# T2103_ValSouffle.net
KiCad netlist of a schematic drawn in EAGLE
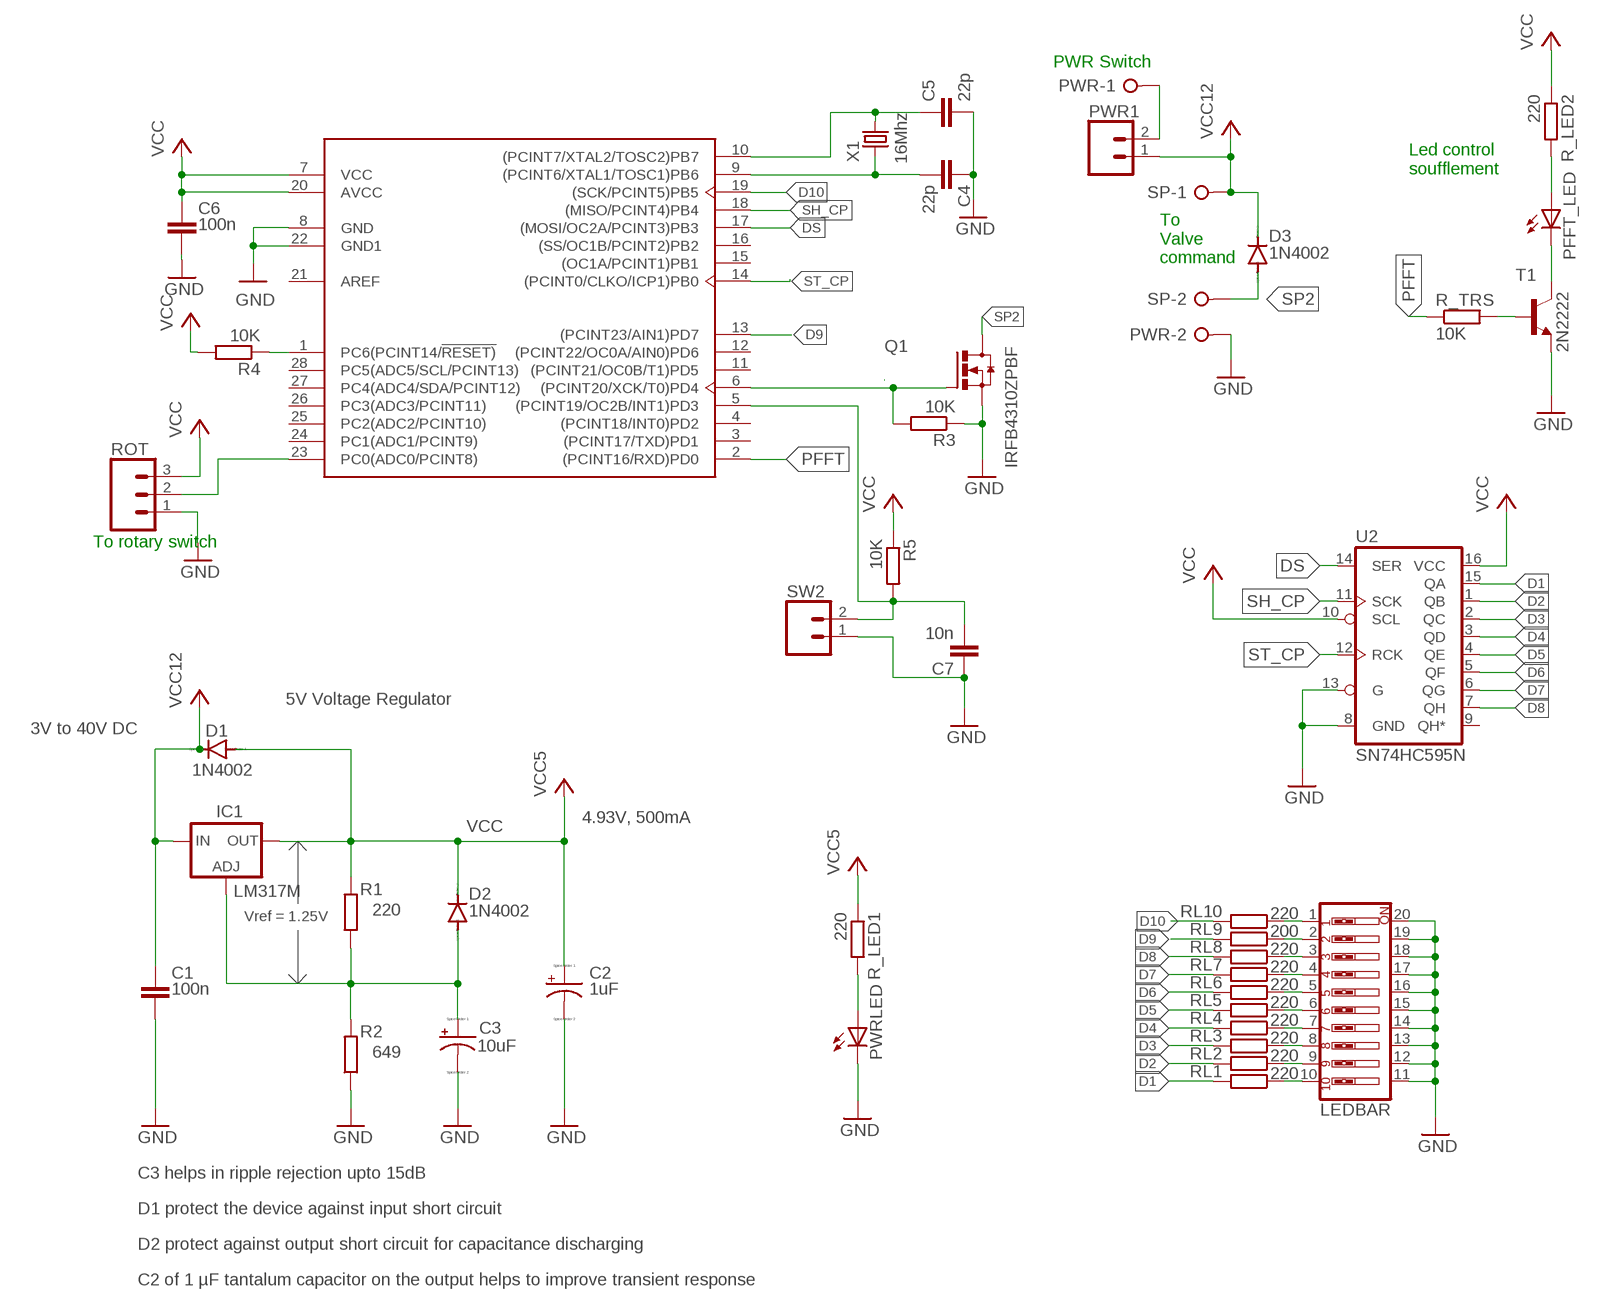
[diagram p0: schematic, sheet 1]

(export (version "E")
  (design (tool "Eeschema 10.0.6"))
  (components
    (comp (ref "C1")
      (value "100n")
      (footprint "eagle-import:C050-030X075")
      (libsource (lib "eagle-import") (part "C-EU050-030X075"))
    )
    (comp (ref "C2")
      (value "1uF")
      (footprint "eagle-import:E1,8-4")
      (libsource (lib "eagle-import") (part "CPOL-USE1.8-4"))
    )
    (comp (ref "C3")
      (value "10uF")
      (footprint "eagle-import:E1,8-4")
      (libsource (lib "eagle-import") (part "CPOL-USE1.8-4"))
    )
    (comp (ref "C4")
      (value "22p")
      (footprint "eagle-import:C025-025X050")
      (libsource (lib "eagle-import") (part "resistor_348_C-EU025-025X050"))
    )
    (comp (ref "C5")
      (value "22p")
      (footprint "eagle-import:C025-025X050")
      (libsource (lib "eagle-import") (part "resistor_348_C-EU025-025X050"))
    )
    (comp (ref "C6")
      (value "100n")
      (footprint "eagle-import:C050-030X075")
      (libsource (lib "eagle-import") (part "C-EU050-030X075"))
    )
    (comp (ref "C7")
      (value "10n")
      (footprint "eagle-import:C025-025X050")
      (libsource (lib "eagle-import") (part "resistor_348_C-EU025-025X050"))
    )
    (comp (ref "D1")
      (value "1N4002")
      (footprint "eagle-import:DO41-10")
      (libsource (lib "eagle-import") (part "1N4004"))
    )
    (comp (ref "D2")
      (value "1N4002")
      (footprint "eagle-import:DO41-10")
      (libsource (lib "eagle-import") (part "1N4004"))
    )
    (comp (ref "D3")
      (value "1N4002")
      (footprint "eagle-import:DO41-10")
      (libsource (lib "eagle-import") (part "1N4004"))
    )
    (comp (ref "IC1")
      (value "LM317MB")
      (footprint "eagle-import:TO220L1")
      (fields (field (name "PARTNUMBER") "LM317M"))
      (libsource (lib "eagle-import") (part "LM317?MB"))
    )
    (comp (ref "LEDBAR")
      (value "SW_DIP-10")
      (footprint "eagle-import:EDG-10")
      (libsource (lib "eagle-import") (part "SW_DIP-10"))
    )
    (comp (ref "PFFT_LED")
      (value "LED5MM")
      (footprint "eagle-import:LED5MM")
      (libsource (lib "eagle-import") (part "LED5MM"))
    )
    (comp (ref "PWR")
      (value "W237-02P")
      (footprint "eagle-import:W237-132")
      (libsource (lib "eagle-import") (part "W237-02P"))
    )
    (comp (ref "PWR1")
      (value "CONN_02")
      (footprint "eagle-import:1X02")
      (libsource (lib "eagle-import") (part "CONN_02"))
    )
    (comp (ref "PWRLED")
      (value "LED5MM")
      (footprint "eagle-import:LED5MM")
      (libsource (lib "eagle-import") (part "LED5MM"))
    )
    (comp (ref "Q1")
      (value "IRFB4310ZPBF")
      (footprint "eagle-import:TO-220")
      (fields
        (field (name "DIGIKEY_PART_NUMBER") "IRF520NPBF-ND")
        (field (name "MANUFACTURER") "Infineon Technologies")
        (field (name "MPN") "IRF520NPBF")
        (field (name "CREATED_BY") "PCBLayout.com")
      )
      (libsource (lib "eagle-import") (part "IRF520NPBF"))
    )
    (comp (ref "R1")
      (value "220")
      (footprint "eagle-import:0207_10")
      (libsource (lib "eagle-import") (part "R-EU_0207/10"))
    )
    (comp (ref "R2")
      (value "649")
      (footprint "eagle-import:0207_10")
      (libsource (lib "eagle-import") (part "R-EU_0207/10"))
    )
    (comp (ref "R3")
      (value "10K")
      (footprint "eagle-import:0207_10")
      (libsource (lib "eagle-import") (part "resistor_348_R-EU_0207/10"))
    )
    (comp (ref "R4")
      (value "10K")
      (footprint "eagle-import:0207_10")
      (libsource (lib "eagle-import") (part "resistor_348_R-EU_0207/10"))
    )
    (comp (ref "R5")
      (value "10K")
      (footprint "eagle-import:0207_10")
      (libsource (lib "eagle-import") (part "resistor_348_R-EU_0207/10"))
    )
    (comp (ref "RL1")
      (value "220")
      (footprint "eagle-import:0207_10")
      (libsource (lib "eagle-import") (part "resistor_348_R-EU_0207/10"))
    )
    (comp (ref "RL2")
      (value "220")
      (footprint "eagle-import:0207_10")
      (libsource (lib "eagle-import") (part "resistor_348_R-EU_0207/10"))
    )
    (comp (ref "RL3")
      (value "220")
      (footprint "eagle-import:0207_10")
      (libsource (lib "eagle-import") (part "resistor_348_R-EU_0207/10"))
    )
    (comp (ref "RL4")
      (value "220")
      (footprint "eagle-import:0207_10")
      (libsource (lib "eagle-import") (part "resistor_348_R-EU_0207/10"))
    )
    (comp (ref "RL5")
      (value "220")
      (footprint "eagle-import:0207_10")
      (libsource (lib "eagle-import") (part "resistor_348_R-EU_0207/10"))
    )
    (comp (ref "RL6")
      (value "220")
      (footprint "eagle-import:0207_10")
      (libsource (lib "eagle-import") (part "resistor_348_R-EU_0207/10"))
    )
    (comp (ref "RL7")
      (value "220")
      (footprint "eagle-import:0207_10")
      (libsource (lib "eagle-import") (part "resistor_348_R-EU_0207/10"))
    )
    (comp (ref "RL8")
      (value "220")
      (footprint "eagle-import:0207_10")
      (libsource (lib "eagle-import") (part "resistor_348_R-EU_0207/10"))
    )
    (comp (ref "RL9")
      (value "200")
      (footprint "eagle-import:0207_10")
      (libsource (lib "eagle-import") (part "resistor_348_R-EU_0207/10"))
    )
    (comp (ref "RL10")
      (value "220")
      (footprint "eagle-import:0207_10")
      (libsource (lib "eagle-import") (part "resistor_348_R-EU_0207/10"))
    )
    (comp (ref "ROT")
      (value "CONN_03")
      (footprint "eagle-import:1X03")
      (libsource (lib "eagle-import") (part "CONN_03"))
    )
    (comp (ref "R_LED1")
      (value "220")
      (footprint "eagle-import:0207_10")
      (libsource (lib "eagle-import") (part "resistor_348_R-EU_0207/10"))
    )
    (comp (ref "R_LED2")
      (value "220")
      (footprint "eagle-import:0207_10")
      (libsource (lib "eagle-import") (part "resistor_348_R-EU_0207/10"))
    )
    (comp (ref "R_TRS")
      (value "10K")
      (footprint "eagle-import:0207_10")
      (libsource (lib "eagle-import") (part "resistor_348_R-EU_0207/10"))
    )
    (comp (ref "SP")
      (value "W237-02P")
      (footprint "eagle-import:W237-132")
      (libsource (lib "eagle-import") (part "W237-02P"))
    )
    (comp (ref "SW2")
      (value "CONN_02")
      (footprint "eagle-import:1X02")
      (libsource (lib "eagle-import") (part "CONN_02"))
    )
    (comp (ref "T1")
      (value "2N2222")
      (footprint "eagle-import:TO92-EBC-OVAL")
      (libsource (lib "eagle-import") (part "2N2222"))
    )
    (comp (ref "U1")
      (value "ATMEGA328P-PU")
      (footprint "eagle-import:DIP-28")
      (fields
        (field (name "DIGIKEY_PART_NUMBER") "ATMEGA328P-PU-ND")
        (field (name "MANUFACTURER") "Microchip Technology")
        (field (name "CREATED_BY") "PCBLayout.com")
      )
      (libsource (lib "eagle-import") (part "ATMEGA328P-PU"))
    )
    (comp (ref "U2")
      (value "SN74HC595N")
      (footprint "eagle-import:DIP16")
      (libsource (lib "eagle-import") (part "74595NHC"))
    )
    (comp (ref "X1")
      (value "16Mhz")
      (footprint "eagle-import:XTAL_HC49")
      (fields
        (field (name "MANUFACTURER") "Xinhunjing ")
        (field (name "MPN") "49S/18PF")
        (field (name "CREATED_BY") "PCBLayout.com")
      )
      (libsource (lib "eagle-import") (part "49S/18PF"))
    )
  )
  (nets
    (net (code "1") (name "D1") (class "Default")
      (node (ref "RL1") (pin "2") (pinfunction "2_2") (pintype "passive"))
      (node (ref "U2") (pin "15") (pinfunction "QA_15") (pintype "tri_state"))
    )
    (net (code "2") (name "D2") (class "Default")
      (node (ref "RL2") (pin "2") (pinfunction "2_2") (pintype "passive"))
      (node (ref "U2") (pin "1") (pinfunction "QB_1") (pintype "tri_state"))
    )
    (net (code "3") (name "D3") (class "Default")
      (node (ref "RL3") (pin "2") (pinfunction "2_2") (pintype "passive"))
      (node (ref "U2") (pin "2") (pinfunction "QC_2") (pintype "tri_state"))
    )
    (net (code "4") (name "D4") (class "Default")
      (node (ref "RL4") (pin "2") (pinfunction "2_2") (pintype "passive"))
      (node (ref "U2") (pin "3") (pinfunction "QD_3") (pintype "tri_state"))
    )
    (net (code "5") (name "D5") (class "Default")
      (node (ref "RL5") (pin "2") (pinfunction "2_2") (pintype "passive"))
      (node (ref "U2") (pin "4") (pinfunction "QE_4") (pintype "tri_state"))
    )
    (net (code "6") (name "D6") (class "Default")
      (node (ref "RL6") (pin "2") (pinfunction "2_2") (pintype "passive"))
      (node (ref "U2") (pin "5") (pinfunction "QF_5") (pintype "tri_state"))
    )
    (net (code "7") (name "D7") (class "Default")
      (node (ref "RL7") (pin "2") (pinfunction "2_2") (pintype "passive"))
      (node (ref "U2") (pin "6") (pinfunction "QG_6") (pintype "tri_state"))
    )
    (net (code "8") (name "D8") (class "Default")
      (node (ref "RL8") (pin "2") (pinfunction "2_2") (pintype "passive"))
      (node (ref "U2") (pin "7") (pinfunction "QH_7") (pintype "tri_state"))
    )
    (net (code "9") (name "D9") (class "Default")
      (node (ref "RL9") (pin "2") (pinfunction "2_2") (pintype "passive"))
      (node (ref "U1") (pin "13") (pinfunction "(PCINT23/AIN1)PD7_13") (pintype "bidirectional"))
    )
    (net (code "10") (name "D10") (class "Default")
      (node (ref "RL10") (pin "2") (pinfunction "2_2") (pintype "passive"))
      (node (ref "U1") (pin "19") (pinfunction "(SCK/PCINT5)PB5_19") (pintype "bidirectional"))
    )
    (net (code "11") (name "DS") (class "Default")
      (node (ref "U1") (pin "17") (pinfunction "(MOSI/OC2A/PCINT3)PB3_17") (pintype "bidirectional"))
      (node (ref "U2") (pin "14") (pinfunction "SER_14") (pintype "input"))
    )
    (net (code "12") (name "GND") (class "Default")
      (node (ref "C1") (pin "2") (pinfunction "2_2") (pintype "passive"))
      (node (ref "C2") (pin "-") (pinfunction "-_-") (pintype "passive"))
      (node (ref "C3") (pin "-") (pinfunction "-_-") (pintype "passive"))
      (node (ref "C4") (pin "1") (pinfunction "1_1") (pintype "passive"))
      (node (ref "C5") (pin "2") (pinfunction "2_2") (pintype "passive"))
      (node (ref "C6") (pin "2") (pinfunction "2_2") (pintype "passive"))
      (node (ref "C7") (pin "1") (pinfunction "1_1") (pintype "passive"))
      (node (ref "LEDBAR") (pin "11") (pinfunction "11_11") (pintype "passive"))
      (node (ref "LEDBAR") (pin "12") (pinfunction "12_12") (pintype "passive"))
      (node (ref "LEDBAR") (pin "13") (pinfunction "13_13") (pintype "passive"))
      (node (ref "LEDBAR") (pin "14") (pinfunction "14_14") (pintype "passive"))
      (node (ref "LEDBAR") (pin "15") (pinfunction "15_15") (pintype "passive"))
      (node (ref "LEDBAR") (pin "16") (pinfunction "16_16") (pintype "passive"))
      (node (ref "LEDBAR") (pin "17") (pinfunction "17_17") (pintype "passive"))
      (node (ref "LEDBAR") (pin "18") (pinfunction "18_18") (pintype "passive"))
      (node (ref "LEDBAR") (pin "19") (pinfunction "19_19") (pintype "passive"))
      (node (ref "LEDBAR") (pin "20") (pinfunction "20_20") (pintype "passive"))
      (node (ref "PWR") (pin "2") (pinfunction "KL_2") (pintype "passive"))
      (node (ref "PWRLED") (pin "K") (pinfunction "C_K") (pintype "passive"))
      (node (ref "Q1") (pin "S") (pinfunction "S_S") (pintype "passive"))
      (node (ref "R2") (pin "1") (pinfunction "1_1") (pintype "passive"))
      (node (ref "R3") (pin "1") (pinfunction "1_1") (pintype "passive"))
      (node (ref "ROT") (pin "1") (pinfunction "1_1") (pintype "passive"))
      (node (ref "SW2") (pin "1") (pinfunction "1_1") (pintype "passive"))
      (node (ref "T1") (pin "E") (pinfunction "E_E") (pintype "passive"))
      (node (ref "U1") (pin "22") (pinfunction "GND1_22") (pintype "power_in"))
      (node (ref "U1") (pin "8") (pinfunction "GND_8") (pintype "power_in"))
      (node (ref "U2") (pin "13") (pinfunction "G_13") (pintype "input"))
      (node (ref "U2") (pin "8") (pinfunction "GND_8") (pintype "power_in"))
    )
    (net (code "13") (name "Net-(IC1-ADJ)") (class "Default")
      (node (ref "C3") (pin "+") (pinfunction "+_+") (pintype "passive"))
      (node (ref "D2") (pin "A") (pinfunction "A_A") (pintype "passive"))
      (node (ref "IC1") (pin "1") (pinfunction "ADJ_1") (pintype "input"))
      (node (ref "R1") (pin "1") (pinfunction "1_1") (pintype "passive"))
      (node (ref "R2") (pin "2") (pinfunction "2_2") (pintype "passive"))
    )
    (net (code "14") (name "Net-(LEDBAR-Pad1)") (class "Default")
      (node (ref "LEDBAR") (pin "1") (pinfunction "1_1") (pintype "passive"))
      (node (ref "RL10") (pin "1") (pinfunction "1_1") (pintype "passive"))
    )
    (net (code "15") (name "Net-(LEDBAR-Pad2)") (class "Default")
      (node (ref "LEDBAR") (pin "2") (pinfunction "2_2") (pintype "passive"))
      (node (ref "RL9") (pin "1") (pinfunction "1_1") (pintype "passive"))
    )
    (net (code "16") (name "Net-(LEDBAR-Pad3)") (class "Default")
      (node (ref "LEDBAR") (pin "3") (pinfunction "3_3") (pintype "passive"))
      (node (ref "RL8") (pin "1") (pinfunction "1_1") (pintype "passive"))
    )
    (net (code "17") (name "Net-(LEDBAR-Pad4)") (class "Default")
      (node (ref "LEDBAR") (pin "4") (pinfunction "4_4") (pintype "passive"))
      (node (ref "RL7") (pin "1") (pinfunction "1_1") (pintype "passive"))
    )
    (net (code "18") (name "Net-(LEDBAR-Pad5)") (class "Default")
      (node (ref "LEDBAR") (pin "5") (pinfunction "5_5") (pintype "passive"))
      (node (ref "RL6") (pin "1") (pinfunction "1_1") (pintype "passive"))
    )
    (net (code "19") (name "Net-(LEDBAR-Pad6)") (class "Default")
      (node (ref "LEDBAR") (pin "6") (pinfunction "6_6") (pintype "passive"))
      (node (ref "RL5") (pin "1") (pinfunction "1_1") (pintype "passive"))
    )
    (net (code "20") (name "Net-(LEDBAR-Pad7)") (class "Default")
      (node (ref "LEDBAR") (pin "7") (pinfunction "7_7") (pintype "passive"))
      (node (ref "RL4") (pin "1") (pinfunction "1_1") (pintype "passive"))
    )
    (net (code "21") (name "Net-(LEDBAR-Pad8)") (class "Default")
      (node (ref "LEDBAR") (pin "8") (pinfunction "8_8") (pintype "passive"))
      (node (ref "RL3") (pin "1") (pinfunction "1_1") (pintype "passive"))
    )
    (net (code "22") (name "Net-(LEDBAR-Pad9)") (class "Default")
      (node (ref "LEDBAR") (pin "9") (pinfunction "9_9") (pintype "passive"))
      (node (ref "RL2") (pin "1") (pinfunction "1_1") (pintype "passive"))
    )
    (net (code "23") (name "Net-(LEDBAR-Pad10)") (class "Default")
      (node (ref "LEDBAR") (pin "10") (pinfunction "10_10") (pintype "passive"))
      (node (ref "RL1") (pin "1") (pinfunction "1_1") (pintype "passive"))
    )
    (net (code "24") (name "Net-(PFFT_LED-C)") (class "Default")
      (node (ref "PFFT_LED") (pin "K") (pinfunction "C_K") (pintype "passive"))
      (node (ref "T1") (pin "C") (pinfunction "C_C") (pintype "passive"))
    )
    (net (code "25") (name "Net-(PFFT_LED-PadA)") (class "Default")
      (node (ref "PFFT_LED") (pin "A") (pinfunction "A_A") (pintype "passive"))
      (node (ref "R_LED2") (pin "2") (pinfunction "2_2") (pintype "passive"))
    )
    (net (code "26") (name "Net-(PWRA-KL)") (class "Default")
      (node (ref "PWR") (pin "1") (pinfunction "KL_1") (pintype "passive"))
      (node (ref "PWR1") (pin "2") (pinfunction "2_2") (pintype "passive"))
    )
    (net (code "27") (name "Net-(PWRLED-PadA)") (class "Default")
      (node (ref "PWRLED") (pin "A") (pinfunction "A_A") (pintype "passive"))
      (node (ref "R_LED1") (pin "2") (pinfunction "2_2") (pintype "passive"))
    )
    (net (code "28") (name "Net-(R_TRS-Pad2)") (class "Default")
      (node (ref "R_TRS") (pin "2") (pinfunction "2_2") (pintype "passive"))
      (node (ref "T1") (pin "B") (pinfunction "B_B") (pintype "passive"))
    )
    (net (code "29") (name "Net-(U1-(PCINT6{slash}XTAL1{slash}TOSC1)PB6)") (class "Default")
      (node (ref "C4") (pin "2") (pinfunction "2_2") (pintype "passive"))
      (node (ref "U1") (pin "9") (pinfunction "(PCINT6/XTAL1/TOSC1)PB6_9") (pintype "bidirectional"))
      (node (ref "X1") (pin "1") (pinfunction "1_1") (pintype "passive"))
    )
    (net (code "30") (name "Net-(U1-(PCINT7{slash}XTAL2{slash}TOSC2)PB7)") (class "Default")
      (node (ref "C5") (pin "1") (pinfunction "1_1") (pintype "passive"))
      (node (ref "U1") (pin "10") (pinfunction "(PCINT7/XTAL2/TOSC2)PB7_10") (pintype "bidirectional"))
      (node (ref "X1") (pin "2") (pinfunction "2_2") (pintype "passive"))
    )
    (net (code "31") (name "Net-(U1-(PCINT19{slash}OC2B{slash}INT1)PD3)") (class "Default")
      (node (ref "C7") (pin "2") (pinfunction "2_2") (pintype "passive"))
      (node (ref "R5") (pin "2") (pinfunction "2_2") (pintype "passive"))
      (node (ref "SW2") (pin "2") (pinfunction "2_2") (pintype "passive"))
      (node (ref "U1") (pin "5") (pinfunction "(PCINT19/OC2B/INT1)PD3_5") (pintype "bidirectional"))
    )
    (net (code "32") (name "Net-(U1-(PCINT20{slash}XCK{slash}T0)PD4)") (class "Default")
      (node (ref "Q1") (pin "G") (pinfunction "G_G") (pintype "passive"))
      (node (ref "R3") (pin "2") (pinfunction "2_2") (pintype "passive"))
      (node (ref "U1") (pin "6") (pinfunction "(PCINT20/XCK/T0)PD4_6") (pintype "bidirectional"))
    )
    (net (code "33") (name "Net-(U1-PC0(ADC0{slash}PCINT8))") (class "Default")
      (node (ref "ROT") (pin "2") (pinfunction "2_2") (pintype "passive"))
      (node (ref "U1") (pin "23") (pinfunction "PC0(ADC0/PCINT8)_23") (pintype "bidirectional"))
    )
    (net (code "34") (name "Net-(U1-PC6(PCINT14{slash}~{RESET}))") (class "Default")
      (node (ref "R4") (pin "1") (pinfunction "1_1") (pintype "passive"))
      (node (ref "U1") (pin "1") (pinfunction "PC6(PCINT14/~{RESET})_1") (pintype "bidirectional"))
    )
    (net (code "35") (name "PFFT") (class "Default")
      (node (ref "R_TRS") (pin "1") (pinfunction "1_1") (pintype "passive"))
      (node (ref "U1") (pin "2") (pinfunction "(PCINT16/RXD)PD0_2") (pintype "bidirectional"))
    )
    (net (code "36") (name "SH_CP") (class "Default")
      (node (ref "U1") (pin "18") (pinfunction "(MISO/PCINT4)PB4_18") (pintype "bidirectional"))
      (node (ref "U2") (pin "11") (pinfunction "SCK_11") (pintype "input"))
    )
    (net (code "37") (name "SP2") (class "Default")
      (node (ref "D3") (pin "A") (pinfunction "A_A") (pintype "passive"))
      (node (ref "Q1") (pin "D") (pinfunction "D_D") (pintype "passive"))
      (node (ref "SP") (pin "2") (pinfunction "KL_2") (pintype "passive"))
    )
    (net (code "38") (name "ST_CP") (class "Default")
      (node (ref "U1") (pin "14") (pinfunction "(PCINT0/CLKO/ICP1)PB0_14") (pintype "bidirectional"))
      (node (ref "U2") (pin "12") (pinfunction "RCK_12") (pintype "input"))
    )
    (net (code "39") (name "VCC") (class "Default")
      (node (ref "C2") (pin "+") (pinfunction "+_+") (pintype "passive"))
      (node (ref "C6") (pin "1") (pinfunction "1_1") (pintype "passive"))
      (node (ref "D1") (pin "A") (pinfunction "A_A") (pintype "passive"))
      (node (ref "D2") (pin "C") (pinfunction "C_C") (pintype "passive"))
      (node (ref "IC1") (pin "2") (pinfunction "OUT_2") (pintype "passive"))
      (node (ref "R1") (pin "2") (pinfunction "2_2") (pintype "passive"))
      (node (ref "R4") (pin "2") (pinfunction "2_2") (pintype "passive"))
      (node (ref "R5") (pin "1") (pinfunction "1_1") (pintype "passive"))
      (node (ref "ROT") (pin "3") (pinfunction "3_3") (pintype "passive"))
      (node (ref "R_LED1") (pin "1") (pinfunction "1_1") (pintype "passive"))
      (node (ref "R_LED2") (pin "1") (pinfunction "1_1") (pintype "passive"))
      (node (ref "U1") (pin "20") (pinfunction "AVCC_20") (pintype "power_in"))
      (node (ref "U1") (pin "7") (pinfunction "VCC_7") (pintype "power_in"))
      (node (ref "U2") (pin "10") (pinfunction "SCL_10") (pintype "input"))
      (node (ref "U2") (pin "16") (pinfunction "VCC_16") (pintype "power_in"))
    )
    (net (code "40") (name "VCC12") (class "Default")
      (node (ref "C1") (pin "1") (pinfunction "1_1") (pintype "passive"))
      (node (ref "D1") (pin "C") (pinfunction "C_C") (pintype "passive"))
      (node (ref "D3") (pin "C") (pinfunction "C_C") (pintype "passive"))
      (node (ref "IC1") (pin "3") (pinfunction "IN_3") (pintype "input"))
      (node (ref "PWR1") (pin "1") (pinfunction "1_1") (pintype "passive"))
      (node (ref "SP") (pin "1") (pinfunction "KL_1") (pintype "passive"))
    )
    (net (code "41") (name "unconnected-(U1-(OC1A{slash}PCINT1)PB1-Pad15)") (class "Default")
      (node (ref "U1") (pin "15") (pinfunction "(OC1A/PCINT1)PB1_15") (pintype "bidirectional"))
    )
    (net (code "42") (name "unconnected-(U1-(PCINT17{slash}TXD)PD1-Pad3)") (class "Default")
      (node (ref "U1") (pin "3") (pinfunction "(PCINT17/TXD)PD1_3") (pintype "bidirectional"))
    )
    (net (code "43") (name "unconnected-(U1-(PCINT18{slash}INT0)PD2-Pad4)") (class "Default")
      (node (ref "U1") (pin "4") (pinfunction "(PCINT18/INT0)PD2_4") (pintype "bidirectional"))
    )
    (net (code "44") (name "unconnected-(U1-(PCINT21{slash}OC0B{slash}T1)PD5-Pad11)") (class "Default")
      (node (ref "U1") (pin "11") (pinfunction "(PCINT21/OC0B/T1)PD5_11") (pintype "bidirectional"))
    )
    (net (code "45") (name "unconnected-(U1-(PCINT22{slash}OC0A{slash}AIN0)PD6-Pad12)") (class "Default")
      (node (ref "U1") (pin "12") (pinfunction "(PCINT22/OC0A/AIN0)PD6_12") (pintype "bidirectional"))
    )
    (net (code "46") (name "unconnected-(U1-(SS{slash}OC1B{slash}PCINT2)PB2-Pad16)") (class "Default")
      (node (ref "U1") (pin "16") (pinfunction "(SS/OC1B/PCINT2)PB2_16") (pintype "bidirectional"))
    )
    (net (code "47") (name "unconnected-(U1-AREF-Pad21)") (class "Default")
      (node (ref "U1") (pin "21") (pinfunction "AREF_21") (pintype "input"))
    )
    (net (code "48") (name "unconnected-(U1-PC1(ADC1{slash}PCINT9)-Pad24)") (class "Default")
      (node (ref "U1") (pin "24") (pinfunction "PC1(ADC1/PCINT9)_24") (pintype "bidirectional"))
    )
    (net (code "49") (name "unconnected-(U1-PC2(ADC2{slash}PCINT10)-Pad25)") (class "Default")
      (node (ref "U1") (pin "25") (pinfunction "PC2(ADC2/PCINT10)_25") (pintype "bidirectional"))
    )
    (net (code "50") (name "unconnected-(U1-PC3(ADC3{slash}PCINT11)-Pad26)") (class "Default")
      (node (ref "U1") (pin "26") (pinfunction "PC3(ADC3/PCINT11)_26") (pintype "bidirectional"))
    )
    (net (code "51") (name "unconnected-(U1-PC4(ADC4{slash}SDA{slash}PCINT12)-Pad27)") (class "Default")
      (node (ref "U1") (pin "27") (pinfunction "PC4(ADC4/SDA/PCINT12)_27") (pintype "bidirectional"))
    )
    (net (code "52") (name "unconnected-(U1-PC5(ADC5{slash}SCL{slash}PCINT13)-Pad28)") (class "Default")
      (node (ref "U1") (pin "28") (pinfunction "PC5(ADC5/SCL/PCINT13)_28") (pintype "bidirectional"))
    )
    (net (code "53") (name "unconnected-(U2-QH*-Pad9)") (class "Default")
      (node (ref "U2") (pin "9") (pinfunction "QH*_9") (pintype "tri_state"))
    )
  )
)
